# etapa1_anger_Y.net
KiCad netlist of a schematic drawn in Altium Designer
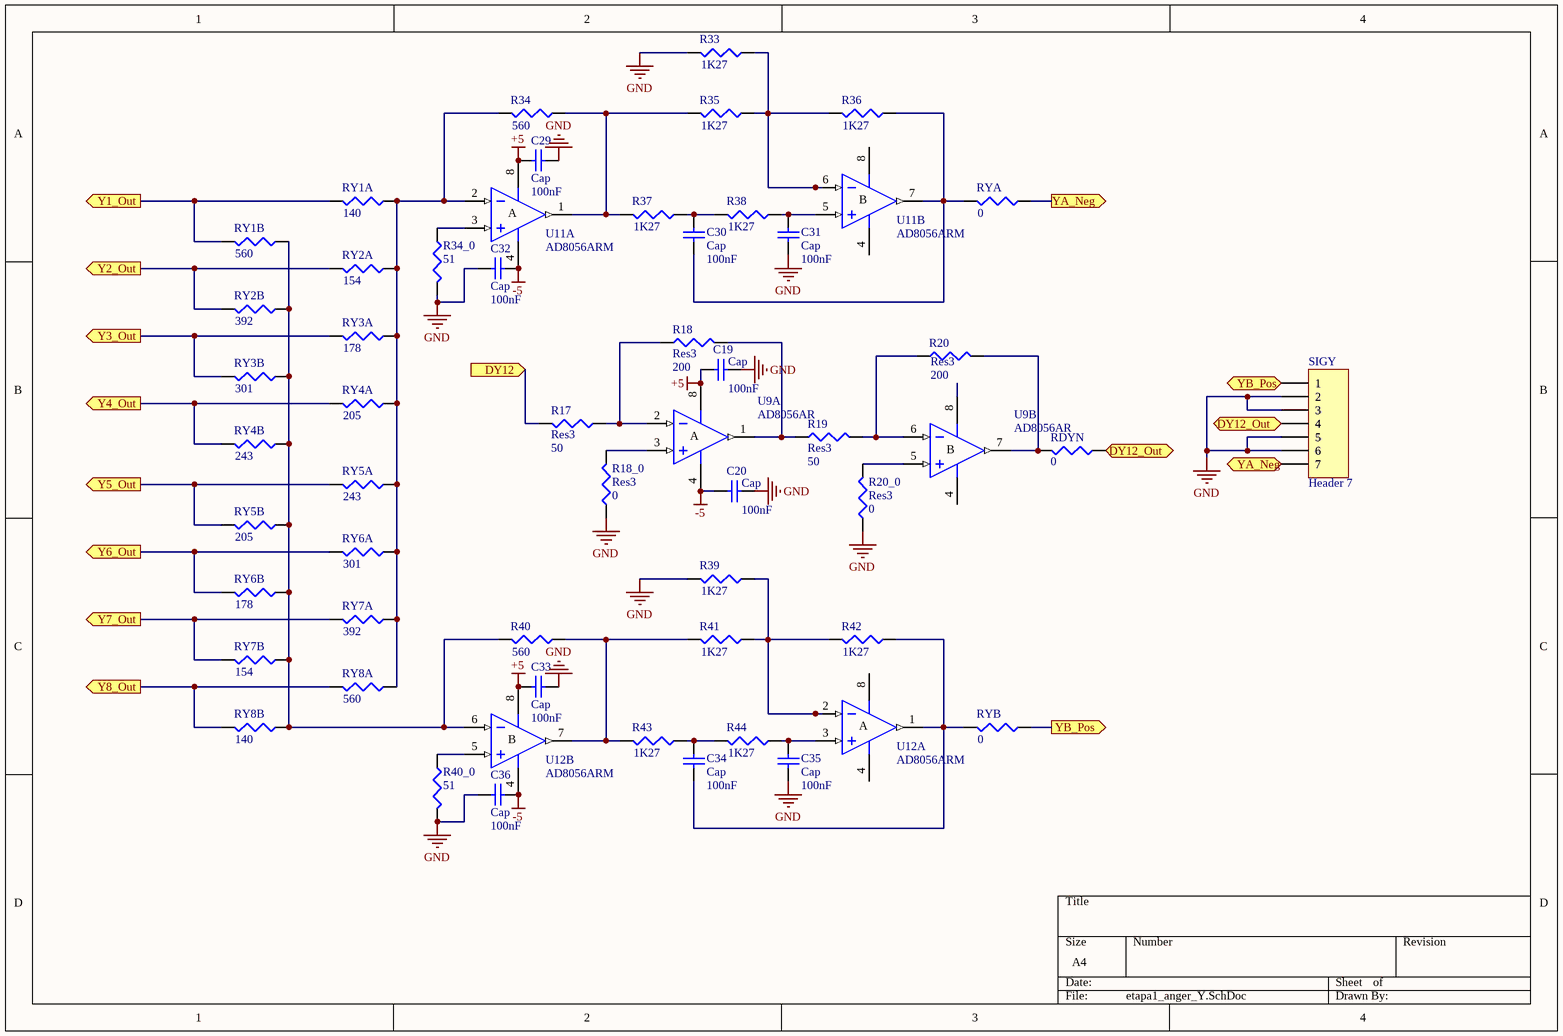
[diagram p0: etapa1_anger_Y.SchDoc]

(export (version "E")
  (design (tool "Eeschema 10.0.6"))
  (components
    (comp (ref "C19")
      (value "Cap")
      (footprint "1608[0603]")
      (description "Capacitor")
      (fields (field (name "ALTIUM_VALUE") "100nF") (field (name "PUBLISHER") "Altium Limited"))
      (libsource (lib "Miscellaneous Devices") (part "Cap"))
    )
    (comp (ref "C20")
      (value "Cap")
      (footprint "1608[0603]")
      (description "Capacitor")
      (fields (field (name "ALTIUM_VALUE") "100nF") (field (name "PUBLISHER") "Altium Limited"))
      (libsource (lib "Miscellaneous Devices") (part "Cap"))
    )
    (comp (ref "C29")
      (value "Cap")
      (footprint "1608[0603]")
      (description "Capacitor")
      (fields (field (name "ALTIUM_VALUE") "100nF") (field (name "PUBLISHER") "Altium Limited"))
      (libsource (lib "Miscellaneous Devices") (part "Cap"))
    )
    (comp (ref "C30")
      (value "Cap")
      (footprint "1608[0603]")
      (description "Capacitor")
      (fields (field (name "ALTIUM_VALUE") "100nF") (field (name "PUBLISHER") "Altium Limited"))
      (libsource (lib "Miscellaneous Devices") (part "Cap"))
    )
    (comp (ref "C31")
      (value "Cap")
      (footprint "1608[0603]")
      (description "Capacitor")
      (fields (field (name "ALTIUM_VALUE") "100nF") (field (name "PUBLISHER") "Altium Limited"))
      (libsource (lib "Miscellaneous Devices") (part "Cap"))
    )
    (comp (ref "C32")
      (value "Cap")
      (footprint "1608[0603]")
      (description "Capacitor")
      (fields (field (name "ALTIUM_VALUE") "100nF") (field (name "PUBLISHER") "Altium Limited"))
      (libsource (lib "Miscellaneous Devices") (part "Cap"))
    )
    (comp (ref "C33")
      (value "Cap")
      (footprint "1608[0603]")
      (description "Capacitor")
      (fields (field (name "ALTIUM_VALUE") "100nF") (field (name "PUBLISHER") "Altium Limited"))
      (libsource (lib "Miscellaneous Devices") (part "Cap"))
    )
    (comp (ref "C34")
      (value "Cap")
      (footprint "1608[0603]")
      (description "Capacitor")
      (fields (field (name "ALTIUM_VALUE") "100nF") (field (name "PUBLISHER") "Altium Limited"))
      (libsource (lib "Miscellaneous Devices") (part "Cap"))
    )
    (comp (ref "C35")
      (value "Cap")
      (footprint "1608[0603]")
      (description "Capacitor")
      (fields (field (name "ALTIUM_VALUE") "100nF") (field (name "PUBLISHER") "Altium Limited"))
      (libsource (lib "Miscellaneous Devices") (part "Cap"))
    )
    (comp (ref "C36")
      (value "Cap")
      (footprint "1608[0603]")
      (description "Capacitor")
      (fields (field (name "ALTIUM_VALUE") "100nF") (field (name "PUBLISHER") "Altium Limited"))
      (libsource (lib "Miscellaneous Devices") (part "Cap"))
    )
    (comp (ref "R17")
      (value "Res3")
      (footprint "0402")
      (description "Resistor")
      (fields (field (name "ALTIUM_VALUE") "50") (field (name "PUBLISHER") "Altium Limited"))
      (libsource (lib "Miscellaneous Devices") (part "Res3"))
    )
    (comp (ref "R18")
      (value "Res3")
      (footprint "0402")
      (description "Resistor")
      (fields (field (name "ALTIUM_VALUE") "200") (field (name "PUBLISHER") "Altium Limited"))
      (libsource (lib "Miscellaneous Devices") (part "Res3"))
    )
    (comp (ref "R18_0")
      (value "Res3")
      (footprint "0402")
      (description "Resistor")
      (fields (field (name "ALTIUM_VALUE") "0") (field (name "PUBLISHER") "Altium Limited"))
      (libsource (lib "Miscellaneous Devices") (part "Res3"))
    )
    (comp (ref "R19")
      (value "Res3")
      (footprint "0402")
      (description "Resistor")
      (fields (field (name "ALTIUM_VALUE") "50") (field (name "PUBLISHER") "Altium Limited"))
      (libsource (lib "Miscellaneous Devices") (part "Res3"))
    )
    (comp (ref "R20")
      (value "Res3")
      (footprint "0402")
      (description "Resistor")
      (fields (field (name "ALTIUM_VALUE") "200") (field (name "PUBLISHER") "Altium Limited"))
      (libsource (lib "Miscellaneous Devices") (part "Res3"))
    )
    (comp (ref "R20_0")
      (value "Res3")
      (footprint "0402")
      (description "Resistor")
      (fields (field (name "ALTIUM_VALUE") "0") (field (name "PUBLISHER") "Altium Limited"))
      (libsource (lib "Miscellaneous Devices") (part "Res3"))
    )
    (comp (ref "R33")
      (value "1K27")
      (footprint "1608[0603]")
      (description "Resistor")
      (fields (field (name "Comment") "Res3") (field (name "PUBLISHER") "Altium Limited"))
      (libsource (lib "Miscellaneous Devices") (part "Res3"))
    )
    (comp (ref "R34")
      (value "560")
      (footprint "0402")
      (description "Resistor")
      (fields (field (name "Comment") "Res3") (field (name "PUBLISHER") "Altium Limited"))
      (libsource (lib "Miscellaneous Devices") (part "Res3"))
    )
    (comp (ref "R34_0")
      (value "51")
      (footprint "0402")
      (description "Resistor")
      (fields (field (name "Comment") "Res3") (field (name "PUBLISHER") "Altium Limited"))
      (libsource (lib "Miscellaneous Devices") (part "Res3"))
    )
    (comp (ref "R35")
      (value "1K27")
      (footprint "0402")
      (description "Resistor")
      (fields (field (name "Comment") "Res3") (field (name "PUBLISHER") "Altium Limited"))
      (libsource (lib "Miscellaneous Devices") (part "Res3"))
    )
    (comp (ref "R36")
      (value "1K27")
      (footprint "0402")
      (description "Resistor")
      (fields (field (name "Comment") "Res3") (field (name "PUBLISHER") "Altium Limited"))
      (libsource (lib "Miscellaneous Devices") (part "Res3"))
    )
    (comp (ref "R37")
      (value "1K27")
      (footprint "0402")
      (description "Resistor")
      (fields (field (name "Comment") "Res3") (field (name "PUBLISHER") "Altium Limited"))
      (libsource (lib "Miscellaneous Devices") (part "Res3"))
    )
    (comp (ref "R38")
      (value "1K27")
      (footprint "0402")
      (description "Resistor")
      (fields (field (name "Comment") "Res3") (field (name "PUBLISHER") "Altium Limited"))
      (libsource (lib "Miscellaneous Devices") (part "Res3"))
    )
    (comp (ref "R39")
      (value "1K27")
      (footprint "1608[0603]")
      (description "Resistor")
      (fields (field (name "Comment") "Res3") (field (name "PUBLISHER") "Altium Limited"))
      (libsource (lib "Miscellaneous Devices") (part "Res3"))
    )
    (comp (ref "R40")
      (value "560")
      (footprint "0402")
      (description "Resistor")
      (fields (field (name "Comment") "Res3") (field (name "PUBLISHER") "Altium Limited"))
      (libsource (lib "Miscellaneous Devices") (part "Res3"))
    )
    (comp (ref "R40_0")
      (value "51")
      (footprint "0402")
      (description "Resistor")
      (fields (field (name "Comment") "Res3") (field (name "PUBLISHER") "Altium Limited"))
      (libsource (lib "Miscellaneous Devices") (part "Res3"))
    )
    (comp (ref "R41")
      (value "1K27")
      (footprint "0402")
      (description "Resistor")
      (fields (field (name "Comment") "Res3") (field (name "PUBLISHER") "Altium Limited"))
      (libsource (lib "Miscellaneous Devices") (part "Res3"))
    )
    (comp (ref "R42")
      (value "1K27")
      (footprint "0402")
      (description "Resistor")
      (fields (field (name "Comment") "Res3") (field (name "PUBLISHER") "Altium Limited"))
      (libsource (lib "Miscellaneous Devices") (part "Res3"))
    )
    (comp (ref "R43")
      (value "1K27")
      (footprint "0402")
      (description "Resistor")
      (fields (field (name "Comment") "Res3") (field (name "PUBLISHER") "Altium Limited"))
      (libsource (lib "Miscellaneous Devices") (part "Res3"))
    )
    (comp (ref "R44")
      (value "1K27")
      (footprint "0402")
      (description "Resistor")
      (fields (field (name "Comment") "Res3") (field (name "PUBLISHER") "Altium Limited"))
      (libsource (lib "Miscellaneous Devices") (part "Res3"))
    )
    (comp (ref "RDYN")
      (value "0")
      (footprint "0402")
      (description "Resistor")
      (fields (field (name "Comment") "Res3") (field (name "PUBLISHER") "Altium Limited"))
      (libsource (lib "Miscellaneous Devices") (part "Res3"))
    )
    (comp (ref "RY1A")
      (value "140")
      (footprint "0402")
      (description "Resistor")
      (fields (field (name "Comment") "Res3") (field (name "PUBLISHER") "Altium Limited"))
      (libsource (lib "Miscellaneous Devices") (part "Res3"))
    )
    (comp (ref "RY1B")
      (value "560")
      (footprint "0402")
      (description "Resistor")
      (fields (field (name "Comment") "Res3") (field (name "PUBLISHER") "Altium Limited"))
      (libsource (lib "Miscellaneous Devices") (part "Res3"))
    )
    (comp (ref "RY2A")
      (value "154")
      (footprint "0402")
      (description "Resistor")
      (fields (field (name "Comment") "Res3") (field (name "PUBLISHER") "Altium Limited"))
      (libsource (lib "Miscellaneous Devices") (part "Res3"))
    )
    (comp (ref "RY2B")
      (value "392")
      (footprint "0402")
      (description "Resistor")
      (fields (field (name "Comment") "Res3") (field (name "PUBLISHER") "Altium Limited"))
      (libsource (lib "Miscellaneous Devices") (part "Res3"))
    )
    (comp (ref "RY3A")
      (value "178")
      (footprint "0402")
      (description "Resistor")
      (fields (field (name "Comment") "Res3") (field (name "PUBLISHER") "Altium Limited"))
      (libsource (lib "Miscellaneous Devices") (part "Res3"))
    )
    (comp (ref "RY3B")
      (value "301")
      (footprint "0402")
      (description "Resistor")
      (fields (field (name "Comment") "Res3") (field (name "PUBLISHER") "Altium Limited"))
      (libsource (lib "Miscellaneous Devices") (part "Res3"))
    )
    (comp (ref "RY4A")
      (value "205")
      (footprint "0402")
      (description "Resistor")
      (fields (field (name "Comment") "Res3") (field (name "PUBLISHER") "Altium Limited"))
      (libsource (lib "Miscellaneous Devices") (part "Res3"))
    )
    (comp (ref "RY4B")
      (value "243")
      (footprint "0402")
      (description "Resistor")
      (fields (field (name "Comment") "Res3") (field (name "PUBLISHER") "Altium Limited"))
      (libsource (lib "Miscellaneous Devices") (part "Res3"))
    )
    (comp (ref "RY5A")
      (value "243")
      (footprint "0402")
      (description "Resistor")
      (fields (field (name "Comment") "Res3") (field (name "PUBLISHER") "Altium Limited"))
      (libsource (lib "Miscellaneous Devices") (part "Res3"))
    )
    (comp (ref "RY5B")
      (value "205")
      (footprint "0402")
      (description "Resistor")
      (fields (field (name "Comment") "Res3") (field (name "PUBLISHER") "Altium Limited"))
      (libsource (lib "Miscellaneous Devices") (part "Res3"))
    )
    (comp (ref "RY6A")
      (value "301")
      (footprint "0402")
      (description "Resistor")
      (fields (field (name "Comment") "Res3") (field (name "PUBLISHER") "Altium Limited"))
      (libsource (lib "Miscellaneous Devices") (part "Res3"))
    )
    (comp (ref "RY6B")
      (value "178")
      (footprint "0402")
      (description "Resistor")
      (fields (field (name "Comment") "Res3") (field (name "PUBLISHER") "Altium Limited"))
      (libsource (lib "Miscellaneous Devices") (part "Res3"))
    )
    (comp (ref "RY7A")
      (value "392")
      (footprint "0402")
      (description "Resistor")
      (fields (field (name "Comment") "Res3") (field (name "PUBLISHER") "Altium Limited"))
      (libsource (lib "Miscellaneous Devices") (part "Res3"))
    )
    (comp (ref "RY7B")
      (value "154")
      (footprint "0402")
      (description "Resistor")
      (fields (field (name "Comment") "Res3") (field (name "PUBLISHER") "Altium Limited"))
      (libsource (lib "Miscellaneous Devices") (part "Res3"))
    )
    (comp (ref "RY8A")
      (value "560")
      (footprint "0402")
      (description "Resistor")
      (fields (field (name "Comment") "Res3") (field (name "PUBLISHER") "Altium Limited"))
      (libsource (lib "Miscellaneous Devices") (part "Res3"))
    )
    (comp (ref "RY8B")
      (value "140")
      (footprint "0402")
      (description "Resistor")
      (fields (field (name "Comment") "Res3") (field (name "PUBLISHER") "Altium Limited"))
      (libsource (lib "Miscellaneous Devices") (part "Res3"))
    )
    (comp (ref "RYA")
      (value "0")
      (footprint "0402")
      (description "Resistor")
      (fields (field (name "Comment") "Res3") (field (name "PUBLISHER") "Altium Limited"))
      (libsource (lib "Miscellaneous Devices") (part "Res3"))
    )
    (comp (ref "RYB")
      (value "0")
      (footprint "0402")
      (description "Resistor")
      (fields (field (name "Comment") "Res3") (field (name "PUBLISHER") "Altium Limited"))
      (libsource (lib "Miscellaneous Devices") (part "Res3"))
    )
    (comp (ref "SIGY")
      (value "Header 7")
      (footprint "HDR1X7")
      (description "Header, 7-Pin")
      (fields (field (name "PUBLISHER") "Altium Limited"))
      (libsource (lib "Miscellaneous Connectors") (part "Header 7"))
    )
    (comp (ref "U9")
      (value "AD8056AR")
      (footprint "RM-8")
      (description "Low Cost, 300MHz Voltage Feedback Amplifier")
      (fields (field (name "PUBLISHER") "Altium Limited"))
      (libsource (lib "AD Operational Amplifier") (part "AD8056AR"))
    )
    (comp (ref "U11")
      (value "AD8056ARM")
      (footprint "RM-8")
      (description "Low Cost, 300MHz Voltage Feedback Amplifier")
      (fields (field (name "PUBLISHER") "Altium Limited"))
      (libsource (lib "AD Operational Amplifier") (part "AD8056ARM"))
    )
    (comp (ref "U12")
      (value "AD8056ARM")
      (footprint "RM-8")
      (description "Low Cost, 300MHz Voltage Feedback Amplifier")
      (fields (field (name "PUBLISHER") "Altium Limited"))
      (libsource (lib "AD Operational Amplifier") (part "AD8056ARM"))
    )
  )
  (nets
    (net (code "1") (name "+5") (class "Default")
      (node (ref "C19") (pin "2") (pinfunction "2_2") (pintype "passive"))
      (node (ref "C29") (pin "1") (pinfunction "1_1") (pintype "passive"))
      (node (ref "C33") (pin "1") (pinfunction "1_1") (pintype "passive"))
      (node (ref "U11") (pin "8") (pinfunction "V+_8") (pintype "power_in"))
      (node (ref "U12") (pin "8") (pinfunction "V+_8") (pintype "power_in"))
      (node (ref "U9") (pin "8") (pinfunction "V+_8") (pintype "power_in"))
    )
    (net (code "2") (name "-5") (class "Default")
      (node (ref "C20") (pin "2") (pinfunction "2_2") (pintype "passive"))
      (node (ref "C32") (pin "2") (pinfunction "2_2") (pintype "passive"))
      (node (ref "C36") (pin "2") (pinfunction "2_2") (pintype "passive"))
      (node (ref "U11") (pin "4") (pinfunction "V-_4") (pintype "power_in"))
      (node (ref "U12") (pin "4") (pinfunction "V-_4") (pintype "power_in"))
      (node (ref "U9") (pin "4") (pinfunction "V-_4") (pintype "power_in"))
    )
    (net (code "3") (name "/DY12") (class "Default")
      (node (ref "R17") (pin "2") (pinfunction "2_2") (pintype "passive"))
    )
    (net (code "4") (name "/DY12_Out") (class "Default")
      (node (ref "RDYN") (pin "1") (pinfunction "1_1") (pintype "passive"))
      (node (ref "SIGY") (pin "4") (pinfunction "4_4") (pintype "passive"))
    )
    (net (code "5") (name "/Y1_Out") (class "Default")
      (node (ref "RY1A") (pin "2") (pinfunction "2_2") (pintype "passive"))
      (node (ref "RY1B") (pin "2") (pinfunction "2_2") (pintype "passive"))
    )
    (net (code "6") (name "/Y2_Out") (class "Default")
      (node (ref "RY2A") (pin "2") (pinfunction "2_2") (pintype "passive"))
      (node (ref "RY2B") (pin "2") (pinfunction "2_2") (pintype "passive"))
    )
    (net (code "7") (name "/Y3_Out") (class "Default")
      (node (ref "RY3A") (pin "2") (pinfunction "2_2") (pintype "passive"))
      (node (ref "RY3B") (pin "2") (pinfunction "2_2") (pintype "passive"))
    )
    (net (code "8") (name "/Y4_Out") (class "Default")
      (node (ref "RY4A") (pin "2") (pinfunction "2_2") (pintype "passive"))
      (node (ref "RY4B") (pin "2") (pinfunction "2_2") (pintype "passive"))
    )
    (net (code "9") (name "/Y5_Out") (class "Default")
      (node (ref "RY5A") (pin "2") (pinfunction "2_2") (pintype "passive"))
      (node (ref "RY5B") (pin "2") (pinfunction "2_2") (pintype "passive"))
    )
    (net (code "10") (name "/Y6_Out") (class "Default")
      (node (ref "RY6A") (pin "2") (pinfunction "2_2") (pintype "passive"))
      (node (ref "RY6B") (pin "2") (pinfunction "2_2") (pintype "passive"))
    )
    (net (code "11") (name "/Y7_Out") (class "Default")
      (node (ref "RY7A") (pin "2") (pinfunction "2_2") (pintype "passive"))
      (node (ref "RY7B") (pin "2") (pinfunction "2_2") (pintype "passive"))
    )
    (net (code "12") (name "/Y8_Out") (class "Default")
      (node (ref "RY8A") (pin "2") (pinfunction "2_2") (pintype "passive"))
      (node (ref "RY8B") (pin "2") (pinfunction "2_2") (pintype "passive"))
    )
    (net (code "13") (name "/YA_Neg") (class "Default")
      (node (ref "RYA") (pin "1") (pinfunction "1_1") (pintype "passive"))
      (node (ref "SIGY") (pin "7") (pinfunction "7_7") (pintype "passive"))
    )
    (net (code "14") (name "/YB_Pos") (class "Default")
      (node (ref "RYB") (pin "1") (pinfunction "1_1") (pintype "passive"))
      (node (ref "SIGY") (pin "1") (pinfunction "1_1") (pintype "passive"))
    )
    (net (code "15") (name "GND") (class "Default")
      (node (ref "C19") (pin "1") (pinfunction "1_1") (pintype "passive"))
      (node (ref "C20") (pin "1") (pinfunction "1_1") (pintype "passive"))
      (node (ref "C29") (pin "2") (pinfunction "2_2") (pintype "passive"))
      (node (ref "C31") (pin "2") (pinfunction "2_2") (pintype "passive"))
      (node (ref "C32") (pin "1") (pinfunction "1_1") (pintype "passive"))
      (node (ref "C33") (pin "2") (pinfunction "2_2") (pintype "passive"))
      (node (ref "C35") (pin "2") (pinfunction "2_2") (pintype "passive"))
      (node (ref "C36") (pin "1") (pinfunction "1_1") (pintype "passive"))
      (node (ref "R18_0") (pin "1") (pinfunction "1_1") (pintype "passive"))
      (node (ref "R20_0") (pin "1") (pinfunction "1_1") (pintype "passive"))
      (node (ref "R33") (pin "2") (pinfunction "2_2") (pintype "passive"))
      (node (ref "R34_0") (pin "2") (pinfunction "2_2") (pintype "passive"))
      (node (ref "R39") (pin "2") (pinfunction "2_2") (pintype "passive"))
      (node (ref "R40_0") (pin "2") (pinfunction "2_2") (pintype "passive"))
      (node (ref "SIGY") (pin "2") (pinfunction "2_2") (pintype "passive"))
      (node (ref "SIGY") (pin "3") (pinfunction "3_3") (pintype "passive"))
      (node (ref "SIGY") (pin "5") (pinfunction "5_5") (pintype "passive"))
      (node (ref "SIGY") (pin "6") (pinfunction "6_6") (pintype "passive"))
    )
    (net (code "16") (name "Net-(C30-Pad1)") (class "Default")
      (node (ref "C30") (pin "1") (pinfunction "1_1") (pintype "passive"))
      (node (ref "R37") (pin "1") (pinfunction "1_1") (pintype "passive"))
      (node (ref "R38") (pin "2") (pinfunction "2_2") (pintype "passive"))
    )
    (net (code "17") (name "Net-(C34-Pad1)") (class "Default")
      (node (ref "C34") (pin "1") (pinfunction "1_1") (pintype "passive"))
      (node (ref "R43") (pin "1") (pinfunction "1_1") (pintype "passive"))
      (node (ref "R44") (pin "2") (pinfunction "2_2") (pintype "passive"))
    )
    (net (code "18") (name "Net-(U9A-IN+)") (class "Default")
      (node (ref "R18_0") (pin "2") (pinfunction "2_2") (pintype "passive"))
      (node (ref "U9") (pin "3") (pinfunction "IN+_3") (pintype "input"))
    )
    (net (code "19") (name "Net-(U9A-IN-)") (class "Default")
      (node (ref "R17") (pin "1") (pinfunction "1_1") (pintype "passive"))
      (node (ref "R18") (pin "1") (pinfunction "1_1") (pintype "passive"))
      (node (ref "U9") (pin "2") (pinfunction "IN-_2") (pintype "input"))
    )
    (net (code "20") (name "Net-(U9A-OUT)") (class "Default")
      (node (ref "R18") (pin "2") (pinfunction "2_2") (pintype "passive"))
      (node (ref "R19") (pin "1") (pinfunction "1_1") (pintype "passive"))
      (node (ref "U9") (pin "1") (pinfunction "OUT_1") (pintype "output"))
    )
    (net (code "21") (name "Net-(U9B-IN+)") (class "Default")
      (node (ref "R20_0") (pin "2") (pinfunction "2_2") (pintype "passive"))
      (node (ref "U9") (pin "5") (pinfunction "IN+_5") (pintype "input"))
    )
    (net (code "22") (name "Net-(U9B-IN-)") (class "Default")
      (node (ref "R19") (pin "2") (pinfunction "2_2") (pintype "passive"))
      (node (ref "R20") (pin "1") (pinfunction "1_1") (pintype "passive"))
      (node (ref "U9") (pin "6") (pinfunction "IN-_6") (pintype "input"))
    )
    (net (code "23") (name "Net-(U9B-OUT)") (class "Default")
      (node (ref "R20") (pin "2") (pinfunction "2_2") (pintype "passive"))
      (node (ref "RDYN") (pin "2") (pinfunction "2_2") (pintype "passive"))
      (node (ref "U9") (pin "7") (pinfunction "OUT_7") (pintype "output"))
    )
    (net (code "24") (name "Net-(U11A-IN+)") (class "Default")
      (node (ref "R34_0") (pin "1") (pinfunction "1_1") (pintype "passive"))
      (node (ref "U11") (pin "3") (pinfunction "IN+_3") (pintype "input"))
    )
    (net (code "25") (name "Net-(U11A-IN-)") (class "Default")
      (node (ref "R34") (pin "2") (pinfunction "2_2") (pintype "passive"))
      (node (ref "RY1A") (pin "1") (pinfunction "1_1") (pintype "passive"))
      (node (ref "RY2A") (pin "1") (pinfunction "1_1") (pintype "passive"))
      (node (ref "RY3A") (pin "1") (pinfunction "1_1") (pintype "passive"))
      (node (ref "RY4A") (pin "1") (pinfunction "1_1") (pintype "passive"))
      (node (ref "RY5A") (pin "1") (pinfunction "1_1") (pintype "passive"))
      (node (ref "RY6A") (pin "1") (pinfunction "1_1") (pintype "passive"))
      (node (ref "RY7A") (pin "1") (pinfunction "1_1") (pintype "passive"))
      (node (ref "RY8A") (pin "1") (pinfunction "1_1") (pintype "passive"))
      (node (ref "U11") (pin "2") (pinfunction "IN-_2") (pintype "input"))
    )
    (net (code "26") (name "Net-(U11A-OUT)") (class "Default")
      (node (ref "R34") (pin "1") (pinfunction "1_1") (pintype "passive"))
      (node (ref "R35") (pin "2") (pinfunction "2_2") (pintype "passive"))
      (node (ref "R37") (pin "2") (pinfunction "2_2") (pintype "passive"))
      (node (ref "U11") (pin "1") (pinfunction "OUT_1") (pintype "output"))
    )
    (net (code "27") (name "Net-(U11B-IN+)") (class "Default")
      (node (ref "C31") (pin "1") (pinfunction "1_1") (pintype "passive"))
      (node (ref "R38") (pin "1") (pinfunction "1_1") (pintype "passive"))
      (node (ref "U11") (pin "5") (pinfunction "IN+_5") (pintype "input"))
    )
    (net (code "28") (name "Net-(U11B-IN-)") (class "Default")
      (node (ref "R33") (pin "1") (pinfunction "1_1") (pintype "passive"))
      (node (ref "R35") (pin "1") (pinfunction "1_1") (pintype "passive"))
      (node (ref "R36") (pin "2") (pinfunction "2_2") (pintype "passive"))
      (node (ref "U11") (pin "6") (pinfunction "IN-_6") (pintype "input"))
    )
    (net (code "29") (name "Net-(U11B-OUT)") (class "Default")
      (node (ref "C30") (pin "2") (pinfunction "2_2") (pintype "passive"))
      (node (ref "R36") (pin "1") (pinfunction "1_1") (pintype "passive"))
      (node (ref "RYA") (pin "2") (pinfunction "2_2") (pintype "passive"))
      (node (ref "U11") (pin "7") (pinfunction "OUT_7") (pintype "output"))
    )
    (net (code "30") (name "Net-(U12A-IN+)") (class "Default")
      (node (ref "C35") (pin "1") (pinfunction "1_1") (pintype "passive"))
      (node (ref "R44") (pin "1") (pinfunction "1_1") (pintype "passive"))
      (node (ref "U12") (pin "3") (pinfunction "IN+_3") (pintype "input"))
    )
    (net (code "31") (name "Net-(U12A-IN-)") (class "Default")
      (node (ref "R39") (pin "1") (pinfunction "1_1") (pintype "passive"))
      (node (ref "R41") (pin "1") (pinfunction "1_1") (pintype "passive"))
      (node (ref "R42") (pin "2") (pinfunction "2_2") (pintype "passive"))
      (node (ref "U12") (pin "2") (pinfunction "IN-_2") (pintype "input"))
    )
    (net (code "32") (name "Net-(U12A-OUT)") (class "Default")
      (node (ref "C34") (pin "2") (pinfunction "2_2") (pintype "passive"))
      (node (ref "R42") (pin "1") (pinfunction "1_1") (pintype "passive"))
      (node (ref "RYB") (pin "2") (pinfunction "2_2") (pintype "passive"))
      (node (ref "U12") (pin "1") (pinfunction "OUT_1") (pintype "output"))
    )
    (net (code "33") (name "Net-(U12B-IN+)") (class "Default")
      (node (ref "R40_0") (pin "1") (pinfunction "1_1") (pintype "passive"))
      (node (ref "U12") (pin "5") (pinfunction "IN+_5") (pintype "input"))
    )
    (net (code "34") (name "Net-(U12B-IN-)") (class "Default")
      (node (ref "R40") (pin "2") (pinfunction "2_2") (pintype "passive"))
      (node (ref "RY1B") (pin "1") (pinfunction "1_1") (pintype "passive"))
      (node (ref "RY2B") (pin "1") (pinfunction "1_1") (pintype "passive"))
      (node (ref "RY3B") (pin "1") (pinfunction "1_1") (pintype "passive"))
      (node (ref "RY4B") (pin "1") (pinfunction "1_1") (pintype "passive"))
      (node (ref "RY5B") (pin "1") (pinfunction "1_1") (pintype "passive"))
      (node (ref "RY6B") (pin "1") (pinfunction "1_1") (pintype "passive"))
      (node (ref "RY7B") (pin "1") (pinfunction "1_1") (pintype "passive"))
      (node (ref "RY8B") (pin "1") (pinfunction "1_1") (pintype "passive"))
      (node (ref "U12") (pin "6") (pinfunction "IN-_6") (pintype "input"))
    )
    (net (code "35") (name "Net-(U12B-OUT)") (class "Default")
      (node (ref "R40") (pin "1") (pinfunction "1_1") (pintype "passive"))
      (node (ref "R41") (pin "2") (pinfunction "2_2") (pintype "passive"))
      (node (ref "R43") (pin "2") (pinfunction "2_2") (pintype "passive"))
      (node (ref "U12") (pin "7") (pinfunction "OUT_7") (pintype "output"))
    )
    (net (code "36") (name "unconnected-(U9B-V+-Pad8)") (class "Default")
      (node (ref "U9") (pin "8") (pinfunction "V+_8") (pintype "power_in"))
    )
    (net (code "37") (name "unconnected-(U9B-V--Pad4)") (class "Default")
      (node (ref "U9") (pin "4") (pinfunction "V-_4") (pintype "power_in"))
    )
    (net (code "38") (name "unconnected-(U11B-V+-Pad8)") (class "Default")
      (node (ref "U11") (pin "8") (pinfunction "V+_8") (pintype "power_in"))
    )
    (net (code "39") (name "unconnected-(U11B-V--Pad4)") (class "Default")
      (node (ref "U11") (pin "4") (pinfunction "V-_4") (pintype "power_in"))
    )
    (net (code "40") (name "unconnected-(U12A-V+-Pad8)") (class "Default")
      (node (ref "U12") (pin "8") (pinfunction "V+_8") (pintype "power_in"))
    )
    (net (code "41") (name "unconnected-(U12A-V--Pad4)") (class "Default")
      (node (ref "U12") (pin "4") (pinfunction "V-_4") (pintype "power_in"))
    )
  )
)
